# 10_-_ETHERNET.net
KiCad netlist of a schematic drawn in Altium Designer
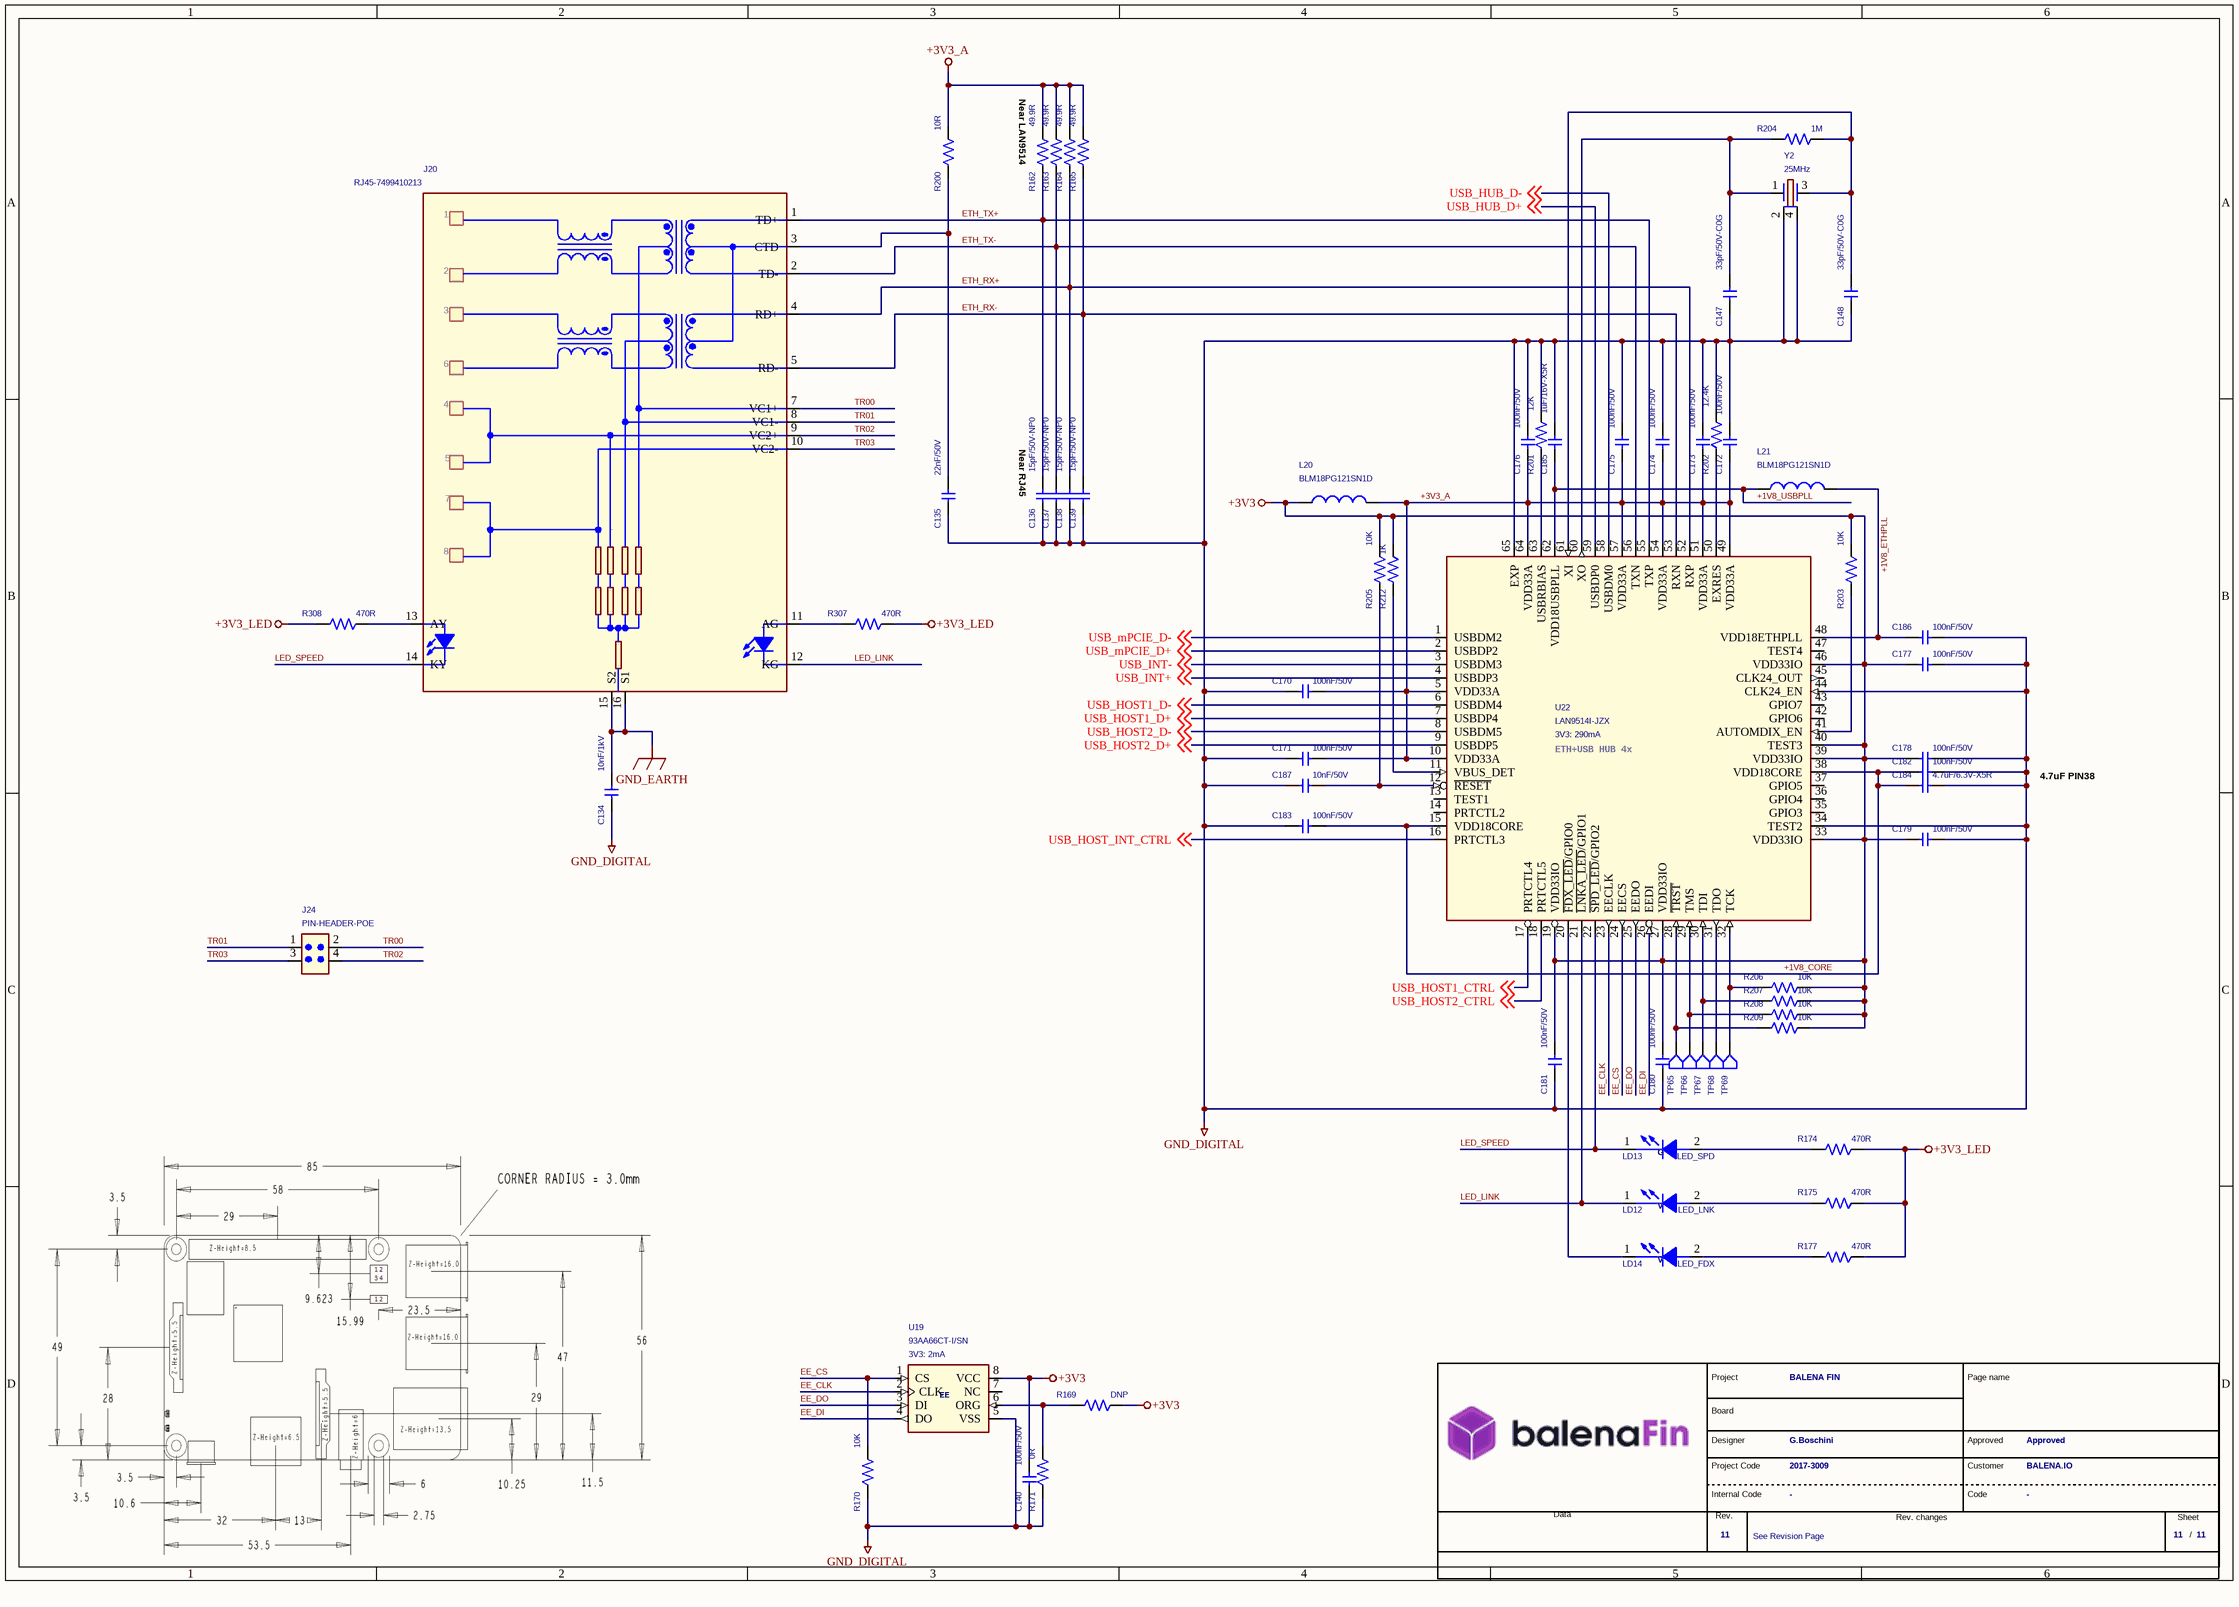
[diagram p0: 10 - ETHERNET.SchDoc]

(export (version "E")
  (design (tool "Eeschema 10.0.6"))
  (components
    (comp (ref "C134")
      (value "10nF/1kV")
      (footprint "CS-C-1206")
      (description "CHIP CAP.CER. 10nF 1000V 10% X7R 1206")
      (fields (field (name "MPN") "Generic"))
      (libsource (lib "*") (part "CS-C-1206-10n/1kV"))
    )
    (comp (ref "C135")
      (value "22nF/50V")
      (footprint "CS-C-0603")
      (description "CHIP CAP.CER. 22nF 50V 10% X7R 0603")
      (fields (field (name "MPN") "Generic"))
      (libsource (lib "*") (part "CS-C-0603-22n/50V"))
    )
    (comp (ref "C136")
      (value "15pF/50V-NP0")
      (footprint "CS-C-0402")
      (description "CHIP CAP.CER. 15pF 50V 5% NPO 0402")
      (fields (field (name "MPN") "Generic"))
      (libsource (lib "*") (part "CS-C-0402-15p/50V-NP0"))
    )
    (comp (ref "C137")
      (value "15pF/50V-NP0")
      (footprint "CS-C-0402")
      (description "CHIP CAP.CER. 15pF 50V 5% NPO 0402")
      (fields (field (name "MPN") "Generic"))
      (libsource (lib "*") (part "CS-C-0402-15p/50V-NP0"))
    )
    (comp (ref "C138")
      (value "15pF/50V-NP0")
      (footprint "CS-C-0402")
      (description "CHIP CAP.CER. 15pF 50V 5% NPO 0402")
      (fields (field (name "MPN") "Generic"))
      (libsource (lib "*") (part "CS-C-0402-15p/50V-NP0"))
    )
    (comp (ref "C139")
      (value "15pF/50V-NP0")
      (footprint "CS-C-0402")
      (description "CHIP CAP.CER. 15pF 50V 5% NPO 0402")
      (fields (field (name "MPN") "Generic"))
      (libsource (lib "*") (part "CS-C-0402-15p/50V-NP0"))
    )
    (comp (ref "C140")
      (value "100nF/50V")
      (footprint "CS-C-0402")
      (description "CHIP CAP.CER. 100nF 16V 10% X7R 0402")
      (fields (field (name "MPN") "Generic"))
      (libsource (lib "*") (part "CS-C-0402-100n/16V"))
    )
    (comp (ref "C147")
      (value "33pF/50V-C0G")
      (footprint "CS-C-0402")
      (description "CHIP CAP.CER. 33pF 50V 5% C0G 0402")
      (fields (field (name "MPN") "Generic"))
      (libsource (lib "*") (part "CS-C-0402-33p/50V-C0G"))
    )
    (comp (ref "C148")
      (value "33pF/50V-C0G")
      (footprint "CS-C-0402")
      (description "CHIP CAP.CER. 33pF 50V 5% C0G 0402")
      (fields (field (name "MPN") "Generic"))
      (libsource (lib "*") (part "CS-C-0402-33p/50V-C0G"))
    )
    (comp (ref "C170")
      (value "100nF/50V")
      (footprint "CS-C-0402")
      (description "CHIP CAP.CER. 100nF 16V 10% X7R 0402")
      (fields (field (name "MPN") "Generic"))
      (libsource (lib "*") (part "CS-C-0402-100n/16V"))
    )
    (comp (ref "C171")
      (value "100nF/50V")
      (footprint "CS-C-0402")
      (description "CHIP CAP.CER. 100nF 16V 10% X7R 0402")
      (fields (field (name "MPN") "Generic"))
      (libsource (lib "*") (part "CS-C-0402-100n/16V"))
    )
    (comp (ref "C172")
      (value "100nF/50V")
      (footprint "CS-C-0402")
      (description "CHIP CAP.CER. 100nF 16V 10% X7R 0402")
      (fields (field (name "MPN") "Generic"))
      (libsource (lib "*") (part "CS-C-0402-100n/16V"))
    )
    (comp (ref "C173")
      (value "100nF/50V")
      (footprint "CS-C-0402")
      (description "CHIP CAP.CER. 100nF 16V 10% X7R 0402")
      (fields (field (name "MPN") "Generic"))
      (libsource (lib "*") (part "CS-C-0402-100n/16V"))
    )
    (comp (ref "C174")
      (value "100nF/50V")
      (footprint "CS-C-0402")
      (description "CHIP CAP.CER. 100nF 16V 10% X7R 0402")
      (fields (field (name "MPN") "Generic"))
      (libsource (lib "*") (part "CS-C-0402-100n/16V"))
    )
    (comp (ref "C175")
      (value "100nF/50V")
      (footprint "CS-C-0402")
      (description "CHIP CAP.CER. 100nF 16V 10% X7R 0402")
      (fields (field (name "MPN") "Generic"))
      (libsource (lib "*") (part "CS-C-0402-100n/16V"))
    )
    (comp (ref "C176")
      (value "100nF/50V")
      (footprint "CS-C-0402")
      (description "CHIP CAP.CER. 100nF 16V 10% X7R 0402")
      (fields (field (name "MPN") "Generic"))
      (libsource (lib "*") (part "CS-C-0402-100n/16V"))
    )
    (comp (ref "C177")
      (value "100nF/50V")
      (footprint "CS-C-0402")
      (description "CHIP CAP.CER. 100nF 16V 10% X7R 0402")
      (fields (field (name "MPN") "Generic"))
      (libsource (lib "*") (part "CS-C-0402-100n/16V"))
    )
    (comp (ref "C178")
      (value "100nF/50V")
      (footprint "CS-C-0402")
      (description "CHIP CAP.CER. 100nF 16V 10% X7R 0402")
      (fields (field (name "MPN") "Generic"))
      (libsource (lib "*") (part "CS-C-0402-100n/16V"))
    )
    (comp (ref "C179")
      (value "100nF/50V")
      (footprint "CS-C-0402")
      (description "CHIP CAP.CER. 100nF 16V 10% X7R 0402")
      (fields (field (name "MPN") "Generic"))
      (libsource (lib "*") (part "CS-C-0402-100n/16V"))
    )
    (comp (ref "C180")
      (value "100nF/50V")
      (footprint "CS-C-0402")
      (description "CHIP CAP.CER. 100nF 16V 10% X7R 0402")
      (fields (field (name "MPN") "Generic"))
      (libsource (lib "*") (part "CS-C-0402-100n/16V"))
    )
    (comp (ref "C181")
      (value "100nF/50V")
      (footprint "CS-C-0402")
      (description "CHIP CAP.CER. 100nF 16V 10% X7R 0402")
      (fields (field (name "MPN") "Generic"))
      (libsource (lib "*") (part "CS-C-0402-100n/16V"))
    )
    (comp (ref "C182")
      (value "100nF/50V")
      (footprint "CS-C-0402")
      (description "CHIP CAP.CER. 100nF 16V 10% X7R 0402")
      (fields (field (name "MPN") "Generic"))
      (libsource (lib "*") (part "CS-C-0402-100n/16V"))
    )
    (comp (ref "C183")
      (value "100nF/50V")
      (footprint "CS-C-0402")
      (description "CHIP CAP.CER. 100nF 16V 10% X7R 0402")
      (fields (field (name "MPN") "Generic"))
      (libsource (lib "*") (part "CS-C-0402-100n/16V"))
    )
    (comp (ref "C184")
      (value "4.7uF/6.3V-X5R")
      (footprint "CS-C-0402")
      (description "CHIP CAP.CER. 4.7uF 6.3V 20% X5R 0402")
      (fields (field (name "MPN") "Generic"))
      (libsource (lib "*") (part "CS-C-0402-4.7u/6V3-X5R"))
    )
    (comp (ref "C185")
      (value "1uF/16V-X5R")
      (footprint "CS-C-0402")
      (description "CHIP CAP.CER. 1uF 16V 10% X5R 0402")
      (fields (field (name "MPN") "Generic"))
      (libsource (lib "*") (part "CS-C-0402-1u/16-X5R"))
    )
    (comp (ref "C186")
      (value "100nF/50V")
      (footprint "CS-C-0402")
      (description "CHIP CAP.CER. 100nF 16V 10% X7R 0402")
      (fields (field (name "MPN") "Generic"))
      (libsource (lib "*") (part "CS-C-0402-100n/16V"))
    )
    (comp (ref "C187")
      (value "10nF/50V")
      (footprint "CS-C-0402")
      (description "CHIP CAP.CER. 10nF 50V 10% X7R 0402")
      (fields (field (name "MPN") "Generic"))
      (libsource (lib "*") (part "CS-C-0402-10n/50V"))
    )
    (comp (ref "J20")
      (value "RJ45-7499410213")
      (footprint "J-RJ45-7499410213")
      (description "CONN JACK 1PORT 100 BASE-T PCB PoE+")
      (fields (field (name "MPN") "7499410213"))
      (libsource (lib "*") (part "RJ45-POE+ - 7499410213"))
    )
    (comp (ref "J24")
      (value "PIN-HEADER-POE")
      (footprint "J-2X2-0254-MDT-TSM")
      (description "CONN HEADER SMT 4POS 2.54MM DUAL ROW")
      (fields (field (name "MPN") "Generic"))
      (libsource (lib "*") (part "STRIP-J-2X2-0254-MDS-TSM"))
    )
    (comp (ref "L20")
      (value "BLM18PG121SN1D")
      (footprint "LS-0603")
      (description "FERRITE BEAD 120 OHM 0603 1LN")
      (libsource (lib "*") (part "FIL-BLM18PG121SN1D-120R/2A"))
    )
    (comp (ref "L21")
      (value "BLM18PG121SN1D")
      (footprint "LS-0603")
      (description "FERRITE BEAD 120 OHM 0603 1LN")
      (libsource (lib "*") (part "FIL-BLM18PG121SN1D-120R/2A"))
    )
    (comp (ref "LD12")
      (value "LED_LNK")
      (footprint "LD-0603")
      (description "LED Green 0603 SMT")
      (fields (field (name "MPN") "Generic"))
      (libsource (lib "*") (part "LED V - GENERICO - 0603"))
    )
    (comp (ref "LD13")
      (value "LED_SPD")
      (footprint "LD-0603")
      (description "LED Yellow 0603 SMT")
      (fields (field (name "MPN") "Generic"))
      (libsource (lib "*") (part "LED G - KPT-1608YC - 0603"))
    )
    (comp (ref "LD14")
      (value "LED_FDX")
      (footprint "LD-0603")
      (description "LED Green 0603 SMT")
      (fields (field (name "MPN") "Generic"))
      (libsource (lib "*") (part "LED V - GENERICO - 0603"))
    )
    (comp (ref "R162")
      (value "49.9R")
      (footprint "RS-0402")
      (description "CHIP RES. 49R9 0402 1/16W 1% 100PPM/°C")
      (fields (field (name "MPN") "Generic"))
      (libsource (lib "*") (part "RS-0402-49.9r"))
    )
    (comp (ref "R163")
      (value "49.9R")
      (footprint "RS-0402")
      (description "CHIP RES. 49R9 0402 1/16W 1% 100PPM/°C")
      (fields (field (name "MPN") "Generic"))
      (libsource (lib "*") (part "RS-0402-49.9r"))
    )
    (comp (ref "R164")
      (value "49.9R")
      (footprint "RS-0402")
      (description "CHIP RES. 49R9 0402 1/16W 1% 100PPM/°C")
      (fields (field (name "MPN") "Generic"))
      (libsource (lib "*") (part "RS-0402-49.9r"))
    )
    (comp (ref "R165")
      (value "49.9R")
      (footprint "RS-0402")
      (description "CHIP RES. 49R9 0402 1/16W 1% 100PPM/°C")
      (fields (field (name "MPN") "Generic"))
      (libsource (lib "*") (part "RS-0402-49.9r"))
    )
    (comp (ref "R169")
      (value "DNP")
      (footprint "RS-0402")
      (description "CHIP RES. 0402")
      (fields (field (name "MPN") "Generic"))
      (libsource (lib "*") (part "RS-0402"))
    )
    (comp (ref "R170")
      (value "10K")
      (footprint "RS-0402")
      (description "CHIP RES. 10K 0402 1/16W 1%")
      (fields (field (name "MPN") "Generic"))
      (libsource (lib "*") (part "RS-0402-10k"))
    )
    (comp (ref "R171")
      (value "0R")
      (footprint "RS-0402")
      (description "CHIP RES. 0R 0402 1/16W 1%")
      (fields (field (name "MPN") "Generic"))
      (libsource (lib "*") (part "RS-0402-0r"))
    )
    (comp (ref "R174")
      (value "470R")
      (footprint "RS-0402")
      (description "CHIP RES. 470R 0402 1/16W 1%")
      (fields (field (name "MPN") "Generic"))
      (libsource (lib "*") (part "RS-0402-470r"))
    )
    (comp (ref "R175")
      (value "470R")
      (footprint "RS-0402")
      (description "CHIP RES. 470R 0402 1/16W 1%")
      (fields (field (name "MPN") "Generic"))
      (libsource (lib "*") (part "RS-0402-470r"))
    )
    (comp (ref "R177")
      (value "470R")
      (footprint "RS-0402")
      (description "CHIP RES. 470R 0402 1/16W 1%")
      (fields (field (name "MPN") "Generic"))
      (libsource (lib "*") (part "RS-0402-470r"))
    )
    (comp (ref "R200")
      (value "10R")
      (footprint "RS-0402")
      (description "CHIP RES. 10R 0402 1/16W 1% 100PPM/°C")
      (fields (field (name "MPN") "Generic"))
      (libsource (lib "*") (part "RS-0402-10r"))
    )
    (comp (ref "R201")
      (value "12K")
      (footprint "RS-0402")
      (description "CHIP RES. 12K 0402 1/16W 1%")
      (fields (field (name "MPN") "Generic"))
      (libsource (lib "*") (part "RS-0402-12k"))
    )
    (comp (ref "R202")
      (value "12.4K")
      (footprint "RS-0402")
      (description "CHIP RES. 12K4 0402 1/16W 1% 100PPM/°C")
      (fields (field (name "MPN") "Generic"))
      (libsource (lib "*") (part "RS-0402-12.4k"))
    )
    (comp (ref "R203")
      (value "10K")
      (footprint "RS-0402")
      (description "CHIP RES. 10K 0402 1/16W 1%")
      (fields (field (name "MPN") "Generic"))
      (libsource (lib "*") (part "RS-0402-10k"))
    )
    (comp (ref "R204")
      (value "1M")
      (footprint "RS-0402")
      (description "CHIP RES. 1M 0402 1/16W 1%")
      (fields (field (name "MPN") "Generic"))
      (libsource (lib "*") (part "RS-0402-1M"))
    )
    (comp (ref "R205")
      (value "10K")
      (footprint "RS-0402")
      (description "CHIP RES. 10K 0402 1/16W 1%")
      (fields (field (name "MPN") "Generic"))
      (libsource (lib "*") (part "RS-0402-10k"))
    )
    (comp (ref "R206")
      (value "10K")
      (footprint "RS-0402")
      (description "CHIP RES. 10K 0402 1/16W 1%")
      (fields (field (name "MPN") "Generic"))
      (libsource (lib "*") (part "RS-0402-10k"))
    )
    (comp (ref "R207")
      (value "10K")
      (footprint "RS-0402")
      (description "CHIP RES. 10K 0402 1/16W 1%")
      (fields (field (name "MPN") "Generic"))
      (libsource (lib "*") (part "RS-0402-10k"))
    )
    (comp (ref "R208")
      (value "10K")
      (footprint "RS-0402")
      (description "CHIP RES. 10K 0402 1/16W 1%")
      (fields (field (name "MPN") "Generic"))
      (libsource (lib "*") (part "RS-0402-10k"))
    )
    (comp (ref "R209")
      (value "10K")
      (footprint "RS-0402")
      (description "CHIP RES. 10K 0402 1/16W 1%")
      (fields (field (name "MPN") "Generic"))
      (libsource (lib "*") (part "RS-0402-10k"))
    )
    (comp (ref "R212")
      (value "1K")
      (footprint "RS-0402")
      (description "CHIP RES. 1K 0402 1/16W 1%")
      (fields (field (name "MPN") "Generic"))
      (libsource (lib "*") (part "RS-0402-1k"))
    )
    (comp (ref "R307")
      (value "470R")
      (footprint "RS-0402")
      (description "CHIP RES. 470R 0402 1/16W 1%")
      (fields (field (name "MPN") "Generic"))
      (libsource (lib "*") (part "RS-0402-470r"))
    )
    (comp (ref "R308")
      (value "470R")
      (footprint "RS-0402")
      (description "CHIP RES. 470R 0402 1/16W 1%")
      (fields (field (name "MPN") "Generic"))
      (libsource (lib "*") (part "RS-0402-470r"))
    )
    (comp (ref "TP65")
      (value "TPS")
      (footprint "TPS-0100")
      (description "TEST POINT SMD")
      (fields (field (name "MPN") "TP-No-BoM"))
      (libsource (lib "*") (part "TEST POINT SMD 1 MM"))
    )
    (comp (ref "TP66")
      (value "TPS")
      (footprint "TPS-0100")
      (description "TEST POINT SMD")
      (fields (field (name "MPN") "TP-No-BoM"))
      (libsource (lib "*") (part "TEST POINT SMD 1 MM"))
    )
    (comp (ref "TP67")
      (value "TPS")
      (footprint "TPS-0100")
      (description "TEST POINT SMD")
      (fields (field (name "MPN") "TP-No-BoM"))
      (libsource (lib "*") (part "TEST POINT SMD 1 MM"))
    )
    (comp (ref "TP68")
      (value "TPS")
      (footprint "TPS-0100")
      (description "TEST POINT SMD")
      (fields (field (name "MPN") "TP-No-BoM"))
      (libsource (lib "*") (part "TEST POINT SMD 1 MM"))
    )
    (comp (ref "TP69")
      (value "TPS")
      (footprint "TPS-0100")
      (description "TEST POINT SMD")
      (fields (field (name "MPN") "TP-No-BoM"))
      (libsource (lib "*") (part "TEST POINT SMD 1 MM"))
    )
    (comp (ref "U19")
      (value "93AA66CT-I/SN")
      (footprint "SOIC8")
      (description "IC EEPROM 4KBIT SPI 3MHZ 8SOIC")
      (fields (field (name "POWER REQUIREMENTS") "3V3: 2mA"))
      (libsource (lib "*") (part "EE - 93AA66CT-I-SN - 4Kb"))
    )
    (comp (ref "U22")
      (value "LAN9514I-JZX")
      (footprint "IC-LAN9514")
      (description "IC USB 2.0 ETH CTLR IND 64-QFN")
      (fields (field (name "POWER REQUIREMENTS") "3V3: 290mA"))
      (libsource (lib "*") (part "USB-ETH-HUBx4 - LAN9514I"))
    )
    (comp (ref "Y2")
      (value "25MHz")
      (footprint "Y-ABM8G")
      (description "25MHz ±20ppm Crystal 18pF 60 Ohms 4-SMD, No Lead  D=3.2x2.5")
      (fields (field (name "MPN") "ABM8G-25.000MHZ- 18-D2Y-T"))
      (libsource (lib "*") (part "QUARZO-ABM8G-25.000MHz"))
    )
  )
  (nets
    (net (code "1") (name "+3V3") (class "Default")
      (node (ref "C140") (pin "1") (pinfunction "1_1") (pintype "passive"))
      (node (ref "C177") (pin "1") (pinfunction "1_1") (pintype "passive"))
      (node (ref "C178") (pin "1") (pinfunction "1_1") (pintype "passive"))
      (node (ref "C179") (pin "1") (pinfunction "1_1") (pintype "passive"))
      (node (ref "C180") (pin "1") (pinfunction "1_1") (pintype "passive"))
      (node (ref "C181") (pin "1") (pinfunction "1_1") (pintype "passive"))
      (node (ref "L20") (pin "1") (pinfunction "1_1") (pintype "passive"))
      (node (ref "R169") (pin "2") (pinfunction "2_2") (pintype "passive"))
      (node (ref "R203") (pin "2") (pinfunction "2_2") (pintype "passive"))
      (node (ref "R205") (pin "2") (pinfunction "2_2") (pintype "passive"))
      (node (ref "R206") (pin "2") (pinfunction "2_2") (pintype "passive"))
      (node (ref "R207") (pin "2") (pinfunction "2_2") (pintype "passive"))
      (node (ref "R208") (pin "2") (pinfunction "2_2") (pintype "passive"))
      (node (ref "R209") (pin "2") (pinfunction "2_2") (pintype "passive"))
      (node (ref "R212") (pin "2") (pinfunction "2_2") (pintype "passive"))
      (node (ref "U19") (pin "8") (pinfunction "VCC_8") (pintype "power_in"))
      (node (ref "U22") (pin "19") (pinfunction "VDD33IO_19") (pintype "power_in"))
      (node (ref "U22") (pin "27") (pinfunction "VDD33IO_27") (pintype "power_in"))
      (node (ref "U22") (pin "33") (pinfunction "VDD33IO_33") (pintype "power_in"))
      (node (ref "U22") (pin "39") (pinfunction "VDD33IO_39") (pintype "power_in"))
      (node (ref "U22") (pin "40") (pinfunction "TEST3_40") (pintype "passive"))
      (node (ref "U22") (pin "46") (pinfunction "VDD33IO_46") (pintype "power_in"))
    )
    (net (code "2") (name "+3V3_A") (class "Default")
      (node (ref "C170") (pin "2") (pinfunction "2_2") (pintype "passive"))
      (node (ref "C171") (pin "2") (pinfunction "2_2") (pintype "passive"))
      (node (ref "C172") (pin "2") (pinfunction "2_2") (pintype "passive"))
      (node (ref "C173") (pin "2") (pinfunction "2_2") (pintype "passive"))
      (node (ref "C174") (pin "2") (pinfunction "2_2") (pintype "passive"))
      (node (ref "C175") (pin "2") (pinfunction "2_2") (pintype "passive"))
      (node (ref "C176") (pin "2") (pinfunction "2_2") (pintype "passive"))
      (node (ref "L20") (pin "2") (pinfunction "2_2") (pintype "passive"))
      (node (ref "R162") (pin "2") (pinfunction "2_2") (pintype "passive"))
      (node (ref "R163") (pin "2") (pinfunction "2_2") (pintype "passive"))
      (node (ref "R164") (pin "2") (pinfunction "2_2") (pintype "passive"))
      (node (ref "R165") (pin "2") (pinfunction "2_2") (pintype "passive"))
      (node (ref "R200") (pin "2") (pinfunction "2_2") (pintype "passive"))
      (node (ref "U22") (pin "10") (pinfunction "VDD33A_10") (pintype "power_in"))
      (node (ref "U22") (pin "49") (pinfunction "VDD33A_49") (pintype "power_in"))
      (node (ref "U22") (pin "5") (pinfunction "VDD33A_5") (pintype "power_in"))
      (node (ref "U22") (pin "51") (pinfunction "VDD33A_51") (pintype "power_in"))
      (node (ref "U22") (pin "54") (pinfunction "VDD33A_54") (pintype "power_in"))
      (node (ref "U22") (pin "57") (pinfunction "VDD33A_57") (pintype "power_in"))
      (node (ref "U22") (pin "64") (pinfunction "VDD33A_64") (pintype "power_in"))
    )
    (net (code "3") (name "+3V3_LED") (class "Default")
      (node (ref "R174") (pin "2") (pinfunction "2_2") (pintype "passive"))
      (node (ref "R175") (pin "2") (pinfunction "2_2") (pintype "passive"))
      (node (ref "R177") (pin "2") (pinfunction "2_2") (pintype "passive"))
      (node (ref "R307") (pin "2") (pinfunction "2_2") (pintype "passive"))
      (node (ref "R308") (pin "1") (pinfunction "1_1") (pintype "passive"))
    )
    (net (code "4") (name "/+1V8_CORE") (class "Default")
      (node (ref "C182") (pin "1") (pinfunction "1_1") (pintype "passive"))
      (node (ref "C183") (pin "2") (pinfunction "2_2") (pintype "passive"))
      (node (ref "C184") (pin "1") (pinfunction "1_1") (pintype "passive"))
      (node (ref "U22") (pin "15") (pinfunction "VDD18CORE_15") (pintype "power_in"))
      (node (ref "U22") (pin "38") (pinfunction "VDD18CORE_38") (pintype "power_in"))
    )
    (net (code "5") (name "/+1V8_ETHPLL") (class "Default")
      (node (ref "C186") (pin "1") (pinfunction "1_1") (pintype "passive"))
      (node (ref "L21") (pin "2") (pinfunction "2_2") (pintype "passive"))
      (node (ref "U22") (pin "48") (pinfunction "VDD18ETHPLL_48") (pintype "power_in"))
    )
    (net (code "6") (name "/+1V8_USBPLL") (class "Default")
      (node (ref "C185") (pin "2") (pinfunction "2_2") (pintype "passive"))
      (node (ref "L21") (pin "1") (pinfunction "1_1") (pintype "passive"))
      (node (ref "U22") (pin "62") (pinfunction "VDD18USBPLL_62") (pintype "power_in"))
    )
    (net (code "7") (name "/EE_CLK") (class "Default")
      (node (ref "U19") (pin "2") (pinfunction "CLK_2") (pintype "input"))
      (node (ref "U22") (pin "23") (pinfunction "EECLK_23") (pintype "output"))
    )
    (net (code "8") (name "/EE_CS") (class "Default")
      (node (ref "R170") (pin "2") (pinfunction "2_2") (pintype "passive"))
      (node (ref "U19") (pin "1") (pinfunction "CS_1") (pintype "input"))
      (node (ref "U22") (pin "24") (pinfunction "EECS_24") (pintype "output"))
    )
    (net (code "9") (name "/EE_DI") (class "Default")
      (node (ref "U19") (pin "4") (pinfunction "DO_4") (pintype "output"))
      (node (ref "U22") (pin "26") (pinfunction "EEDI_26") (pintype "input"))
    )
    (net (code "10") (name "/EE_DO") (class "Default")
      (node (ref "U19") (pin "3") (pinfunction "DI_3") (pintype "input"))
      (node (ref "U22") (pin "25") (pinfunction "EEDO_25") (pintype "output"))
    )
    (net (code "11") (name "/ETH_RX+") (class "Default")
      (node (ref "C138") (pin "1") (pinfunction "1_1") (pintype "passive"))
      (node (ref "J20") (pin "4") (pinfunction "RD+_4") (pintype "passive"))
      (node (ref "R164") (pin "1") (pinfunction "1_1") (pintype "passive"))
      (node (ref "U22") (pin "52") (pinfunction "RXP_52") (pintype "bidirectional"))
    )
    (net (code "12") (name "/ETH_RX-") (class "Default")
      (node (ref "C139") (pin "1") (pinfunction "1_1") (pintype "passive"))
      (node (ref "J20") (pin "5") (pinfunction "RD-_5") (pintype "passive"))
      (node (ref "R165") (pin "1") (pinfunction "1_1") (pintype "passive"))
      (node (ref "U22") (pin "53") (pinfunction "RXN_53") (pintype "bidirectional"))
    )
    (net (code "13") (name "/ETH_TX+") (class "Default")
      (node (ref "C136") (pin "1") (pinfunction "1_1") (pintype "passive"))
      (node (ref "J20") (pin "1") (pinfunction "TD+_1") (pintype "passive"))
      (node (ref "R162") (pin "1") (pinfunction "1_1") (pintype "passive"))
      (node (ref "U22") (pin "55") (pinfunction "TXP_55") (pintype "bidirectional"))
    )
    (net (code "14") (name "/ETH_TX-") (class "Default")
      (node (ref "C137") (pin "1") (pinfunction "1_1") (pintype "passive"))
      (node (ref "J20") (pin "2") (pinfunction "TD-_2") (pintype "passive"))
      (node (ref "R163") (pin "1") (pinfunction "1_1") (pintype "passive"))
      (node (ref "U22") (pin "56") (pinfunction "TXN_56") (pintype "bidirectional"))
    )
    (net (code "15") (name "/LED_LINK") (class "Default")
      (node (ref "J20") (pin "12") (pinfunction "KG_12") (pintype "passive"))
      (node (ref "LD12") (pin "1") (pinfunction "C_1") (pintype "passive"))
      (node (ref "U22") (pin "21") (pinfunction "~{LNKA_LED}/GPIO1_21") (pintype "passive"))
    )
    (net (code "16") (name "/LED_SPEED") (class "Default")
      (node (ref "J20") (pin "14") (pinfunction "KY_14") (pintype "passive"))
      (node (ref "LD13") (pin "1") (pinfunction "C_1") (pintype "passive"))
      (node (ref "U22") (pin "22") (pinfunction "~{SPD_LED}/GPIO2_22") (pintype "passive"))
    )
    (net (code "17") (name "/TR00") (class "Default")
      (node (ref "J20") (pin "7") (pinfunction "VC1+_7") (pintype "passive"))
      (node (ref "J24") (pin "2") (pinfunction "2_2") (pintype "passive"))
    )
    (net (code "18") (name "/TR01") (class "Default")
      (node (ref "J20") (pin "8") (pinfunction "VC1-_8") (pintype "passive"))
      (node (ref "J24") (pin "1") (pinfunction "1_1") (pintype "passive"))
    )
    (net (code "19") (name "/TR02") (class "Default")
      (node (ref "J20") (pin "9") (pinfunction "VC2+_9") (pintype "passive"))
      (node (ref "J24") (pin "4") (pinfunction "4_4") (pintype "passive"))
    )
    (net (code "20") (name "/TR03") (class "Default")
      (node (ref "J20") (pin "10") (pinfunction "VC2-_10") (pintype "passive"))
      (node (ref "J24") (pin "3") (pinfunction "3_3") (pintype "passive"))
    )
    (net (code "21") (name "GND_DIGITAL") (class "Default")
      (node (ref "C134") (pin "1") (pinfunction "1_1") (pintype "passive"))
      (node (ref "C135") (pin "2") (pinfunction "2_2") (pintype "passive"))
      (node (ref "C136") (pin "2") (pinfunction "2_2") (pintype "passive"))
      (node (ref "C137") (pin "2") (pinfunction "2_2") (pintype "passive"))
      (node (ref "C138") (pin "2") (pinfunction "2_2") (pintype "passive"))
      (node (ref "C139") (pin "2") (pinfunction "2_2") (pintype "passive"))
      (node (ref "C140") (pin "2") (pinfunction "2_2") (pintype "passive"))
      (node (ref "C147") (pin "2") (pinfunction "2_2") (pintype "passive"))
      (node (ref "C148") (pin "2") (pinfunction "2_2") (pintype "passive"))
      (node (ref "C170") (pin "1") (pinfunction "1_1") (pintype "passive"))
      (node (ref "C171") (pin "1") (pinfunction "1_1") (pintype "passive"))
      (node (ref "C172") (pin "1") (pinfunction "1_1") (pintype "passive"))
      (node (ref "C173") (pin "1") (pinfunction "1_1") (pintype "passive"))
      (node (ref "C174") (pin "1") (pinfunction "1_1") (pintype "passive"))
      (node (ref "C175") (pin "1") (pinfunction "1_1") (pintype "passive"))
      (node (ref "C176") (pin "1") (pinfunction "1_1") (pintype "passive"))
      (node (ref "C177") (pin "2") (pinfunction "2_2") (pintype "passive"))
      (node (ref "C178") (pin "2") (pinfunction "2_2") (pintype "passive"))
      (node (ref "C179") (pin "2") (pinfunction "2_2") (pintype "passive"))
      (node (ref "C180") (pin "2") (pinfunction "2_2") (pintype "passive"))
      (node (ref "C181") (pin "2") (pinfunction "2_2") (pintype "passive"))
      (node (ref "C182") (pin "2") (pinfunction "2_2") (pintype "passive"))
      (node (ref "C183") (pin "1") (pinfunction "1_1") (pintype "passive"))
      (node (ref "C184") (pin "2") (pinfunction "2_2") (pintype "passive"))
      (node (ref "C185") (pin "1") (pinfunction "1_1") (pintype "passive"))
      (node (ref "C186") (pin "2") (pinfunction "2_2") (pintype "passive"))
      (node (ref "C187") (pin "1") (pinfunction "1_1") (pintype "passive"))
      (node (ref "R170") (pin "1") (pinfunction "1_1") (pintype "passive"))
      (node (ref "R171") (pin "1") (pinfunction "1_1") (pintype "passive"))
      (node (ref "R201") (pin "2") (pinfunction "2_2") (pintype "passive"))
      (node (ref "R202") (pin "2") (pinfunction "2_2") (pintype "passive"))
      (node (ref "U19") (pin "5") (pinfunction "VSS_5") (pintype "power_in"))
      (node (ref "U22") (pin "34") (pinfunction "TEST2_34") (pintype "passive"))
      (node (ref "U22") (pin "44") (pinfunction "CLK24_EN_44") (pintype "input"))
      (node (ref "U22") (pin "65") (pinfunction "EXP_65") (pintype "passive"))
      (node (ref "Y2") (pin "2") (pinfunction "2_2") (pintype "passive"))
      (node (ref "Y2") (pin "4") (pinfunction "4_4") (pintype "passive"))
    )
    (net (code "22") (name "GND_EARTH") (class "Default")
      (node (ref "C134") (pin "2") (pinfunction "2_2") (pintype "passive"))
      (node (ref "J20") (pin "15") (pinfunction "S2_15") (pintype "passive"))
      (node (ref "J20") (pin "16") (pinfunction "S1_16") (pintype "passive"))
    )
    (net (code "23") (name "Net-(J20-AG)") (class "Default")
      (node (ref "J20") (pin "11") (pinfunction "AG_11") (pintype "passive"))
      (node (ref "R307") (pin "1") (pinfunction "1_1") (pintype "passive"))
    )
    (net (code "24") (name "Net-(J20-AY)") (class "Default")
      (node (ref "J20") (pin "13") (pinfunction "AY_13") (pintype "passive"))
      (node (ref "R308") (pin "2") (pinfunction "2_2") (pintype "passive"))
    )
    (net (code "25") (name "Net-(J20-CTD)") (class "Default")
      (node (ref "C135") (pin "1") (pinfunction "1_1") (pintype "passive"))
      (node (ref "J20") (pin "3") (pinfunction "CTD_3") (pintype "passive"))
      (node (ref "R200") (pin "1") (pinfunction "1_1") (pintype "passive"))
    )
    (net (code "26") (name "Net-(LD12-A)") (class "Default")
      (node (ref "LD12") (pin "2") (pinfunction "A_2") (pintype "passive"))
      (node (ref "R175") (pin "1") (pinfunction "1_1") (pintype "passive"))
    )
    (net (code "27") (name "Net-(LD13-A)") (class "Default")
      (node (ref "LD13") (pin "2") (pinfunction "A_2") (pintype "passive"))
      (node (ref "R174") (pin "1") (pinfunction "1_1") (pintype "passive"))
    )
    (net (code "28") (name "Net-(LD14-A)") (class "Default")
      (node (ref "LD14") (pin "2") (pinfunction "A_2") (pintype "passive"))
      (node (ref "R177") (pin "1") (pinfunction "1_1") (pintype "passive"))
    )
    (net (code "29") (name "Net-(LD14-C)") (class "Default")
      (node (ref "LD14") (pin "1") (pinfunction "C_1") (pintype "passive"))
      (node (ref "U22") (pin "20") (pinfunction "~{FDX_LED}/GPIO0_20") (pintype "passive"))
    )
    (net (code "30") (name "Net-(TP65-TP)") (class "Default")
      (node (ref "R209") (pin "1") (pinfunction "1_1") (pintype "passive"))
      (node (ref "TP65") (pin "1") (pinfunction "TP_1") (pintype "passive"))
      (node (ref "U22") (pin "28") (pinfunction "~{TRST}_28") (pintype "input"))
    )
    (net (code "31") (name "Net-(TP66-TP)") (class "Default")
      (node (ref "R208") (pin "1") (pinfunction "1_1") (pintype "passive"))
      (node (ref "TP66") (pin "1") (pinfunction "TP_1") (pintype "passive"))
      (node (ref "U22") (pin "29") (pinfunction "TMS_29") (pintype "input"))
    )
    (net (code "32") (name "Net-(TP67-TP)") (class "Default")
      (node (ref "R207") (pin "1") (pinfunction "1_1") (pintype "passive"))
      (node (ref "TP67") (pin "1") (pinfunction "TP_1") (pintype "passive"))
      (node (ref "U22") (pin "30") (pinfunction "TDI_30") (pintype "input"))
    )
    (net (code "33") (name "Net-(TP68-TP)") (class "Default")
      (node (ref "TP68") (pin "1") (pinfunction "TP_1") (pintype "passive"))
      (node (ref "U22") (pin "31") (pinfunction "TDO_31") (pintype "output"))
    )
    (net (code "34") (name "Net-(TP69-TP)") (class "Default")
      (node (ref "R206") (pin "1") (pinfunction "1_1") (pintype "passive"))
      (node (ref "TP69") (pin "1") (pinfunction "TP_1") (pintype "passive"))
      (node (ref "U22") (pin "32") (pinfunction "TCK_32") (pintype "input"))
    )
    (net (code "35") (name "Net-(U19-ORG)") (class "Default")
      (node (ref "R169") (pin "1") (pinfunction "1_1") (pintype "passive"))
      (node (ref "R171") (pin "2") (pinfunction "2_2") (pintype "passive"))
      (node (ref "U19") (pin "6") (pinfunction "ORG_6") (pintype "input"))
    )
    (net (code "36") (name "Net-(U22-AUTOMDIX_EN)") (class "Default")
      (node (ref "R203") (pin "1") (pinfunction "1_1") (pintype "passive"))
      (node (ref "U22") (pin "41") (pinfunction "AUTOMDIX_EN_41") (pintype "input"))
    )
    (net (code "37") (name "Net-(U22-EXRES)") (class "Default")
      (node (ref "R202") (pin "1") (pinfunction "1_1") (pintype "passive"))
      (node (ref "U22") (pin "50") (pinfunction "EXRES_50") (pintype "passive"))
    )
    (net (code "38") (name "Net-(U22-USBRBIAS)") (class "Default")
      (node (ref "R201") (pin "1") (pinfunction "1_1") (pintype "passive"))
      (node (ref "U22") (pin "63") (pinfunction "USBRBIAS_63") (pintype "passive"))
    )
    (net (code "39") (name "Net-(U22-VBUS_DET)") (class "Default")
      (node (ref "R212") (pin "1") (pinfunction "1_1") (pintype "passive"))
      (node (ref "U22") (pin "11") (pinfunction "VBUS_DET_11") (pintype "input"))
    )
    (net (code "40") (name "Net-(U22-XI)") (class "Default")
      (node (ref "C148") (pin "1") (pinfunction "1_1") (pintype "passive"))
      (node (ref "R204") (pin "2") (pinfunction "2_2") (pintype "passive"))
      (node (ref "U22") (pin "61") (pinfunction "XI_61") (pintype "input"))
      (node (ref "Y2") (pin "3") (pinfunction "3_3") (pintype "passive"))
    )
    (net (code "41") (name "Net-(U22-XO)") (class "Default")
      (node (ref "C147") (pin "1") (pinfunction "1_1") (pintype "passive"))
      (node (ref "R204") (pin "1") (pinfunction "1_1") (pintype "passive"))
      (node (ref "U22") (pin "60") (pinfunction "XO_60") (pintype "output"))
      (node (ref "Y2") (pin "1") (pinfunction "1_1") (pintype "passive"))
    )
    (net (code "42") (name "Net-(U22-~{RESET})") (class "Default")
      (node (ref "C187") (pin "2") (pinfunction "2_2") (pintype "passive"))
      (node (ref "R205") (pin "1") (pinfunction "1_1") (pintype "passive"))
      (node (ref "U22") (pin "12") (pinfunction "~{RESET}_12") (pintype "input"))
    )
    (net (code "43") (name "USB_HOST1_CTRL") (class "Default")
      (node (ref "U22") (pin "17") (pinfunction "PRTCTL4_17") (pintype "passive"))
    )
    (net (code "44") (name "USB_HOST1_D+") (class "Default")
      (node (ref "U22") (pin "7") (pinfunction "USBDP4_7") (pintype "bidirectional"))
    )
    (net (code "45") (name "USB_HOST1_D-") (class "Default")
      (node (ref "U22") (pin "6") (pinfunction "USBDM4_6") (pintype "bidirectional"))
    )
    (net (code "46") (name "USB_HOST2_CTRL") (class "Default")
      (node (ref "U22") (pin "18") (pinfunction "PRTCTL5_18") (pintype "passive"))
    )
    (net (code "47") (name "USB_HOST2_D+") (class "Default")
      (node (ref "U22") (pin "9") (pinfunction "USBDP5_9") (pintype "bidirectional"))
    )
    (net (code "48") (name "USB_HOST2_D-") (class "Default")
      (node (ref "U22") (pin "8") (pinfunction "USBDM5_8") (pintype "bidirectional"))
    )
    (net (code "49") (name "USB_HOST_INT_CTRL") (class "Default")
      (node (ref "U22") (pin "16") (pinfunction "PRTCTL3_16") (pintype "passive"))
    )
    (net (code "50") (name "USB_HUB_D+") (class "Default")
      (node (ref "U22") (pin "59") (pinfunction "USBDP0_59") (pintype "bidirectional"))
    )
    (net (code "51") (name "USB_HUB_D-") (class "Default")
      (node (ref "U22") (pin "58") (pinfunction "USBDM0_58") (pintype "bidirectional"))
    )
    (net (code "52") (name "USB_INT+") (class "Default")
      (node (ref "U22") (pin "4") (pinfunction "USBDP3_4") (pintype "bidirectional"))
    )
    (net (code "53") (name "USB_INT-") (class "Default")
      (node (ref "U22") (pin "3") (pinfunction "USBDM3_3") (pintype "bidirectional"))
    )
    (net (code "54") (name "USB_mPCIE_D+") (class "Default")
      (node (ref "U22") (pin "2") (pinfunction "USBDP2_2") (pintype "bidirectional"))
    )
    (net (code "55") (name "USB_mPCIE_D-") (class "Default")
      (node (ref "U22") (pin "1") (pinfunction "USBDM2_1") (pintype "bidirectional"))
    )
    (net (code "56") (name "unconnected-(U19-NC-Pad7)") (class "Default")
      (node (ref "U19") (pin "7") (pinfunction "NC_7") (pintype "passive"))
    )
    (net (code "57") (name "unconnected-(U22-CLK24_OUT-Pad45)") (class "Default")
      (node (ref "U22") (pin "45") (pinfunction "CLK24_OUT_45") (pintype "output"))
    )
    (net (code "58") (name "unconnected-(U22-GPIO3-Pad35)") (class "Default")
      (node (ref "U22") (pin "35") (pinfunction "GPIO3_35") (pintype "bidirectional"))
    )
    (net (code "59") (name "unconnected-(U22-GPIO4-Pad36)") (class "Default")
      (node (ref "U22") (pin "36") (pinfunction "GPIO4_36") (pintype "bidirectional"))
    )
    (net (code "60") (name "unconnected-(U22-GPIO5-Pad37)") (class "Default")
      (node (ref "U22") (pin "37") (pinfunction "GPIO5_37") (pintype "bidirectional"))
    )
    (net (code "61") (name "unconnected-(U22-GPIO6-Pad42)") (class "Default")
      (node (ref "U22") (pin "42") (pinfunction "GPIO6_42") (pintype "bidirectional"))
    )
    (net (code "62") (name "unconnected-(U22-GPIO7-Pad43)") (class "Default")
      (node (ref "U22") (pin "43") (pinfunction "GPIO7_43") (pintype "bidirectional"))
    )
    (net (code "63") (name "unconnected-(U22-PRTCTL2-Pad14)") (class "Default")
      (node (ref "U22") (pin "14") (pinfunction "PRTCTL2_14") (pintype "passive"))
    )
    (net (code "64") (name "unconnected-(U22-TEST1-Pad13)") (class "Default")
      (node (ref "U22") (pin "13") (pinfunction "TEST1_13") (pintype "passive"))
    )
    (net (code "65") (name "unconnected-(U22-TEST4-Pad47)") (class "Default")
      (node (ref "U22") (pin "47") (pinfunction "TEST4_47") (pintype "passive"))
    )
  )
)
